# Arm_Power_Distro_Board.net
KiCad netlist of a schematic drawn in Altium Designer
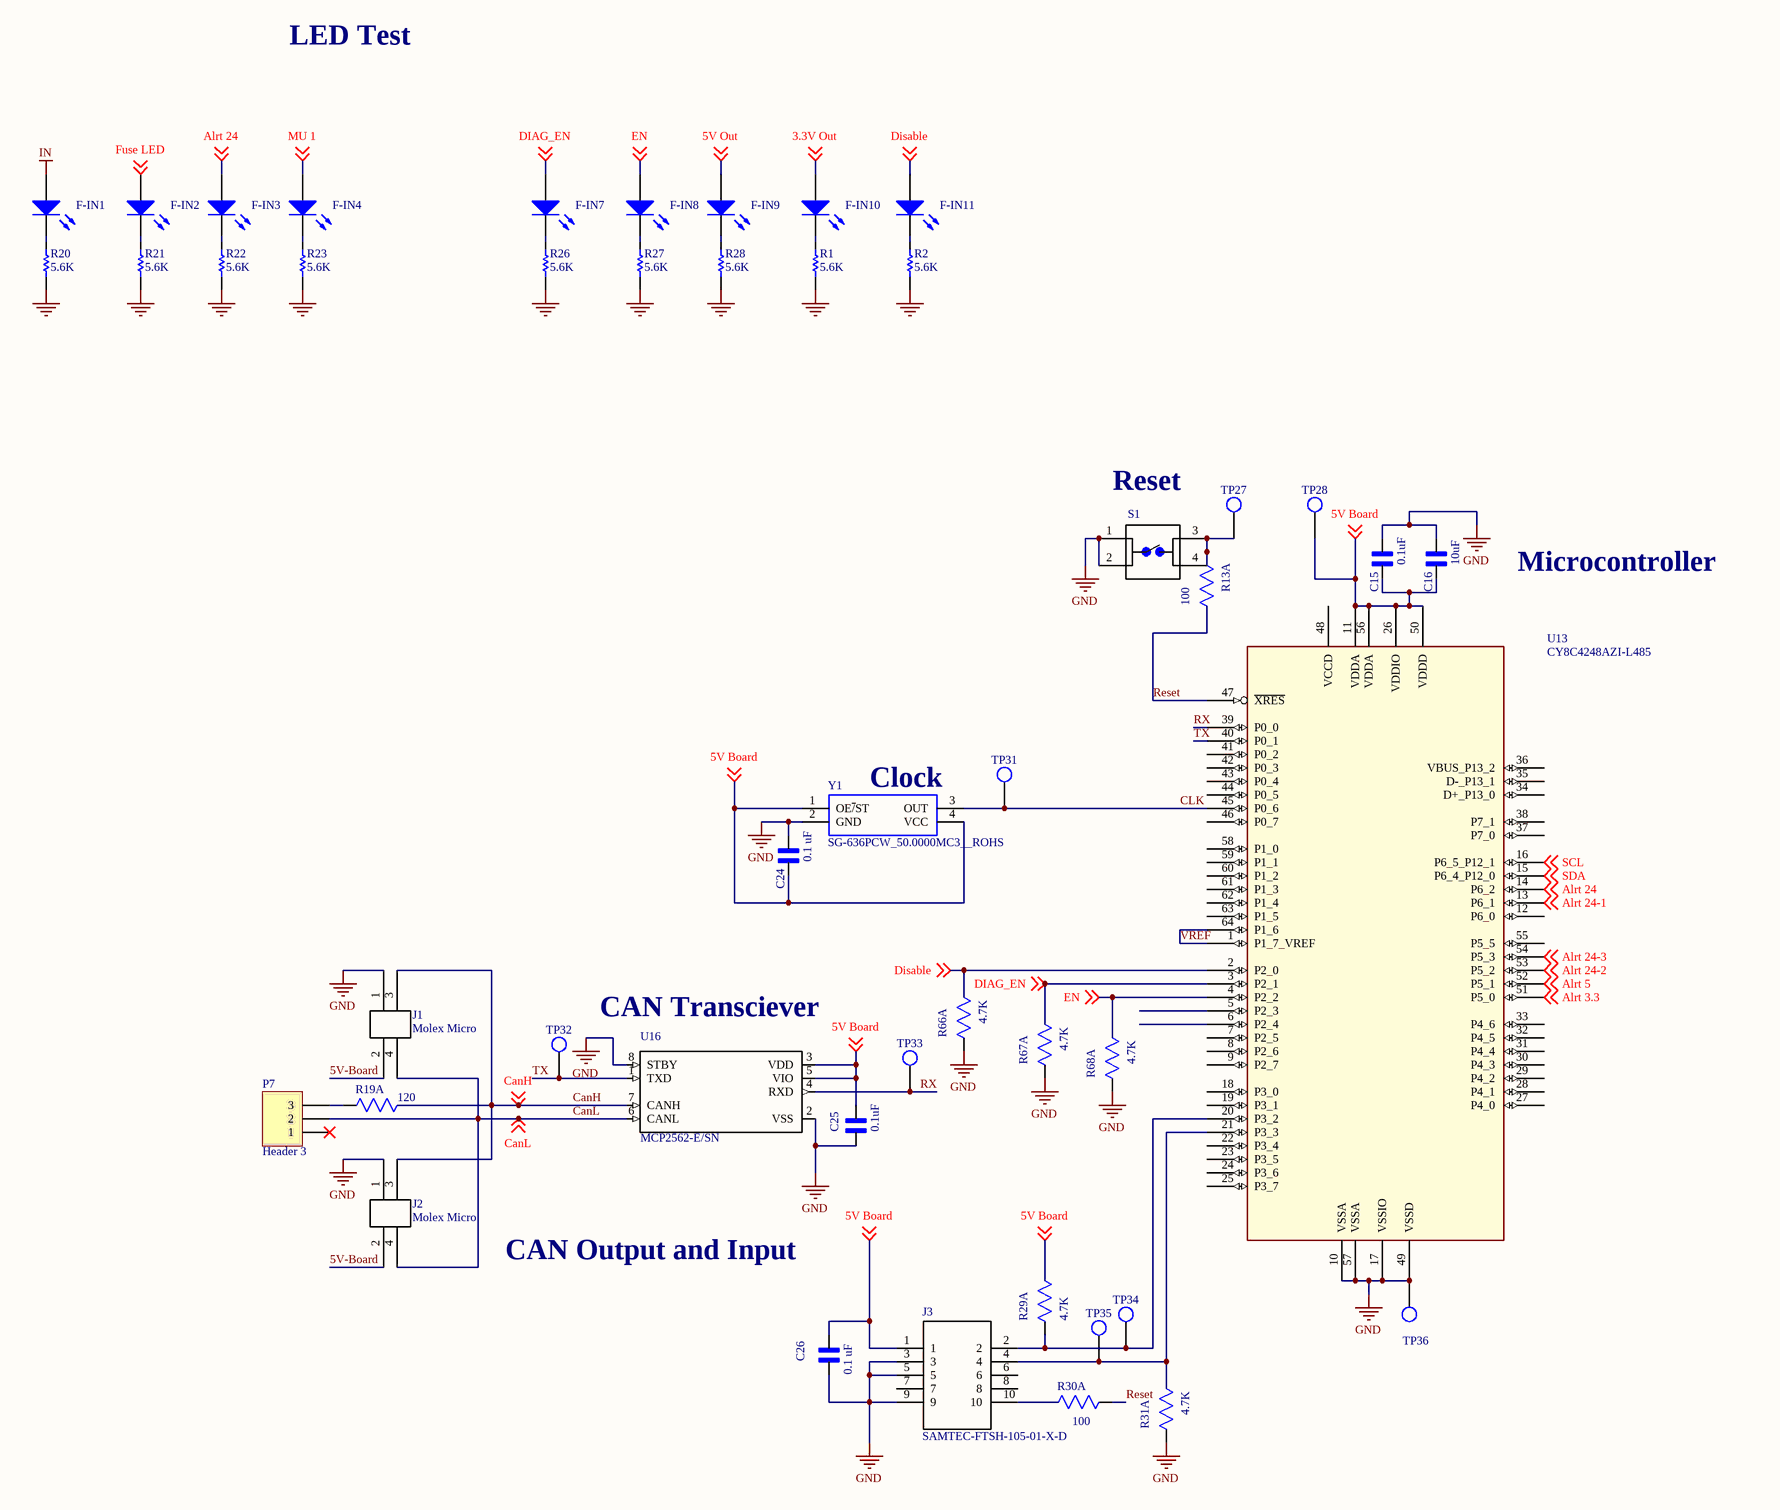
[diagram p0: Arm Power Distro Board (A).SchDoc]

(export (version "E")
  (design (tool "Eeschema 10.0.6"))
  (components
    (comp (ref "C15")
      (value "0.1uF")
      (footprint "*CAPC2012X135N")
      (description "Cap Ceramic 2.2uF 16V X5R 10% SMD 0805 125Â°C Embossed T/R")
      (fields (field (name "MP") "EMK212BJ225KG-T") (field (name "DIGI-KEY_PART_NUMBER") "587-1293-1-ND"))
      (libsource (lib "EMK212BJ225KG-T") (part "EMK212BJ225KG-T"))
    )
    (comp (ref "C16")
      (value "10uF")
      (footprint "*CAPC2012X135N")
      (description "Cap Ceramic 2.2uF 16V X5R 10% SMD 0805 125Â°C Embossed T/R")
      (fields (field (name "MP") "EMK212BJ225KG-T") (field (name "DIGI-KEY_PART_NUMBER") "587-1293-1-ND"))
      (libsource (lib "EMK212BJ225KG-T") (part "EMK212BJ225KG-T"))
    )
    (comp (ref "C24")
      (value "0.1 uF")
      (footprint "*CAPC2012X135N")
      (description "Cap Ceramic 2.2uF 16V X5R 10% SMD 0805 125Â°C Embossed T/R")
      (fields (field (name "MP") "EMK212BJ225KG-T") (field (name "DIGI-KEY_PART_NUMBER") "587-1293-1-ND"))
      (libsource (lib "EMK212BJ225KG-T") (part "EMK212BJ225KG-T"))
    )
    (comp (ref "C25")
      (value "0.1uF")
      (footprint "*CAPC2012X135N")
      (description "Cap Ceramic 2.2uF 16V X5R 10% SMD 0805 125Â°C Embossed T/R")
      (fields (field (name "MP") "EMK212BJ225KG-T") (field (name "DIGI-KEY_PART_NUMBER") "587-1293-1-ND"))
      (libsource (lib "EMK212BJ225KG-T") (part "EMK212BJ225KG-T"))
    )
    (comp (ref "C26")
      (value "0.1 uF")
      (footprint "*CAPC2012X135N")
      (description "Cap Ceramic 2.2uF 16V X5R 10% SMD 0805 125Â°C Embossed T/R")
      (fields (field (name "MP") "EMK212BJ225KG-T") (field (name "DIGI-KEY_PART_NUMBER") "587-1293-1-ND"))
      (libsource (lib "EMK212BJ225KG-T") (part "EMK212BJ225KG-T"))
    )
    (comp (ref "F-IN1")
      (value "150060VS75000")
      (footprint "0603_A")
      (description "SMD mono-color Chip LED, WL-SMCW, Bright Green")
      (fields (field (name "MANUFACTURER") "Wuerth Elektronik"))
      (libsource (lib "Altium Content Vault") (part "WE-LED_K1A2-2"))
    )
    (comp (ref "F-IN2")
      (value "150060VS75000")
      (footprint "0603_A")
      (description "SMD mono-color Chip LED, WL-SMCW, Bright Green")
      (fields (field (name "MANUFACTURER") "Wuerth Elektronik"))
      (libsource (lib "Altium Content Vault") (part "WE-LED_K1A2-2"))
    )
    (comp (ref "F-IN3")
      (value "150060VS75000")
      (footprint "0603_A")
      (description "SMD mono-color Chip LED, WL-SMCW, Bright Green")
      (fields (field (name "MANUFACTURER") "Wuerth Elektronik"))
      (libsource (lib "Altium Content Vault") (part "WE-LED_K1A2-2"))
    )
    (comp (ref "F-IN4")
      (value "150060VS75000")
      (footprint "0603_A")
      (description "SMD mono-color Chip LED, WL-SMCW, Bright Green")
      (fields (field (name "MANUFACTURER") "Wuerth Elektronik"))
      (libsource (lib "Altium Content Vault") (part "WE-LED_K1A2-2"))
    )
    (comp (ref "F-IN7")
      (value "150060VS75000")
      (footprint "0603_A")
      (description "SMD mono-color Chip LED, WL-SMCW, Bright Green")
      (fields (field (name "MANUFACTURER") "Wuerth Elektronik"))
      (libsource (lib "Altium Content Vault") (part "WE-LED_K1A2-2"))
    )
    (comp (ref "F-IN8")
      (value "150060VS75000")
      (footprint "0603_A")
      (description "SMD mono-color Chip LED, WL-SMCW, Bright Green")
      (fields (field (name "MANUFACTURER") "Wuerth Elektronik"))
      (libsource (lib "Altium Content Vault") (part "WE-LED_K1A2-2"))
    )
    (comp (ref "F-IN9")
      (value "150060VS75000")
      (footprint "0603_A")
      (description "SMD mono-color Chip LED, WL-SMCW, Bright Green")
      (fields (field (name "MANUFACTURER") "Wuerth Elektronik"))
      (libsource (lib "Altium Content Vault") (part "WE-LED_K1A2-2"))
    )
    (comp (ref "F-IN10")
      (value "150060VS75000")
      (footprint "0603_A")
      (description "SMD mono-color Chip LED, WL-SMCW, Bright Green")
      (fields (field (name "MANUFACTURER") "Wuerth Elektronik"))
      (libsource (lib "Altium Content Vault") (part "WE-LED_K1A2-2"))
    )
    (comp (ref "F-IN11")
      (value "150060VS75000")
      (footprint "0603_A")
      (description "SMD mono-color Chip LED, WL-SMCW, Bright Green")
      (fields (field (name "MANUFACTURER") "Wuerth Elektronik"))
      (libsource (lib "Altium Content Vault") (part "WE-LED_K1A2-2"))
    )
    (comp (ref "J1")
      (value "Molex Micro")
      (footprint "0430450427")
      (description "Molex micro-fit 3.0, P/N 0430450427")
      (libsource (lib "Connector Schematic Symbols") (part "Molex micro-fit 4-pin (dual row schematic)"))
    )
    (comp (ref "J2")
      (value "Molex Micro")
      (footprint "0430450427")
      (description "Molex micro-fit 3.0, P/N 0430450427")
      (libsource (lib "Connector Schematic Symbols") (part "Molex micro-fit 4-pin (dual row schematic)"))
    )
    (comp (ref "J3")
      (value "SAMTEC-FTSH-105-01-X-D")
      (footprint "SAMTEC-FTSH-105-01-X-D")
      (libsource (lib "Connector Schematic Symbols") (part "SAMTEC-FTSH-105-01-X-D"))
    )
    (comp (ref "P7")
      (value "Header 3")
      (footprint "HDR1X3")
      (description "Header, 3-Pin")
      (fields (field (name "PUBLISHER") "Altium Limited"))
      (libsource (lib "Miscellaneous Connectors") (part "Header 3"))
    )
    (comp (ref "R1")
      (value "5.6K")
      (footprint "RESC2013X60X35ML10T20")
      (description "RES SMD 36K OHM 1% 1/8W 0805")
      (fields (field (name "MANUFACTURER") "Yageo") (field (name "PART NUMBER") "RC0805FR-0736KL"))
      (libsource (lib "Altium Content Vault") (part "RES"))
    )
    (comp (ref "R2")
      (value "5.6K")
      (footprint "RESC2013X60X35ML10T20")
      (description "RES SMD 36K OHM 1% 1/8W 0805")
      (fields (field (name "MANUFACTURER") "Yageo") (field (name "PART NUMBER") "RC0805FR-0736KL"))
      (libsource (lib "Altium Content Vault") (part "RES"))
    )
    (comp (ref "R13")
      (value "100")
      (footprint "RC0805N")
      (description "No Description Available")
      (fields
        (field (name "MANUFACTURER_PART_NUMBER") "CRCW0805681RFKEA_1")
        (field (name "COPYRIGHT") "Copyright (C) 2018 Accelerated Designs. All rights reserved")
      )
      (libsource (lib "2019-11-21_04-54-07") (part "CRCW0805681RFKEA"))
    )
    (comp (ref "R19")
      (value "120")
      (footprint "RC0805N")
      (description "No Description Available")
      (fields
        (field (name "MANUFACTURER_PART_NUMBER") "CRCW0805681RFKEA_1")
        (field (name "COPYRIGHT") "Copyright (C) 2018 Accelerated Designs. All rights reserved")
      )
      (libsource (lib "2019-11-21_04-54-07") (part "CRCW0805681RFKEA"))
    )
    (comp (ref "R20")
      (value "5.6K")
      (footprint "RESC2013X60X35ML10T20")
      (description "RES SMD 36K OHM 1% 1/8W 0805")
      (fields (field (name "MANUFACTURER") "Yageo") (field (name "PART NUMBER") "RC0805FR-0736KL"))
      (libsource (lib "Altium Content Vault") (part "RES"))
    )
    (comp (ref "R21")
      (value "5.6K")
      (footprint "RESC2013X60X35ML10T20")
      (description "RES SMD 36K OHM 1% 1/8W 0805")
      (fields (field (name "MANUFACTURER") "Yageo") (field (name "PART NUMBER") "RC0805FR-0736KL"))
      (libsource (lib "Altium Content Vault") (part "RES"))
    )
    (comp (ref "R22")
      (value "5.6K")
      (footprint "RESC2013X60X35ML10T20")
      (description "RES SMD 36K OHM 1% 1/8W 0805")
      (fields (field (name "MANUFACTURER") "Yageo") (field (name "PART NUMBER") "RC0805FR-0736KL"))
      (libsource (lib "Altium Content Vault") (part "RES"))
    )
    (comp (ref "R23")
      (value "5.6K")
      (footprint "RESC2013X60X35ML10T20")
      (description "RES SMD 36K OHM 1% 1/8W 0805")
      (fields (field (name "MANUFACTURER") "Yageo") (field (name "PART NUMBER") "RC0805FR-0736KL"))
      (libsource (lib "Altium Content Vault") (part "RES"))
    )
    (comp (ref "R26")
      (value "5.6K")
      (footprint "RESC2013X60X35ML10T20")
      (description "RES SMD 36K OHM 1% 1/8W 0805")
      (fields (field (name "MANUFACTURER") "Yageo") (field (name "PART NUMBER") "RC0805FR-0736KL"))
      (libsource (lib "Altium Content Vault") (part "RES"))
    )
    (comp (ref "R27")
      (value "5.6K")
      (footprint "RESC2013X60X35ML10T20")
      (description "RES SMD 36K OHM 1% 1/8W 0805")
      (fields (field (name "MANUFACTURER") "Yageo") (field (name "PART NUMBER") "RC0805FR-0736KL"))
      (libsource (lib "Altium Content Vault") (part "RES"))
    )
    (comp (ref "R28")
      (value "5.6K")
      (footprint "RESC2013X60X35ML10T20")
      (description "RES SMD 36K OHM 1% 1/8W 0805")
      (fields (field (name "MANUFACTURER") "Yageo") (field (name "PART NUMBER") "RC0805FR-0736KL"))
      (libsource (lib "Altium Content Vault") (part "RES"))
    )
    (comp (ref "R29")
      (value "4.7K")
      (footprint "RC0805N")
      (description "No Description Available")
      (fields
        (field (name "MANUFACTURER_PART_NUMBER") "CRCW0805681RFKEA_1")
        (field (name "COPYRIGHT") "Copyright (C) 2018 Accelerated Designs. All rights reserved")
      )
      (libsource (lib "2019-11-21_04-54-07") (part "CRCW0805681RFKEA"))
    )
    (comp (ref "R30")
      (value "100")
      (footprint "RC0805N")
      (description "No Description Available")
      (fields
        (field (name "MANUFACTURER_PART_NUMBER") "CRCW0805681RFKEA_1")
        (field (name "COPYRIGHT") "Copyright (C) 2018 Accelerated Designs. All rights reserved")
      )
      (libsource (lib "2019-11-21_04-54-07") (part "CRCW0805681RFKEA"))
    )
    (comp (ref "R31")
      (value "4.7K")
      (footprint "RC0805N")
      (description "No Description Available")
      (fields
        (field (name "MANUFACTURER_PART_NUMBER") "CRCW0805681RFKEA_1")
        (field (name "COPYRIGHT") "Copyright (C) 2018 Accelerated Designs. All rights reserved")
      )
      (libsource (lib "2019-11-21_04-54-07") (part "CRCW0805681RFKEA"))
    )
    (comp (ref "R66")
      (value "4.7K")
      (footprint "RC0805N")
      (description "No Description Available")
      (fields
        (field (name "MANUFACTURER_PART_NUMBER") "CRCW0805681RFKEA_1")
        (field (name "COPYRIGHT") "Copyright (C) 2018 Accelerated Designs. All rights reserved")
      )
      (libsource (lib "2019-11-21_04-54-07") (part "CRCW0805681RFKEA"))
    )
    (comp (ref "R67")
      (value "4.7K")
      (footprint "RC0805N")
      (description "No Description Available")
      (fields
        (field (name "MANUFACTURER_PART_NUMBER") "CRCW0805681RFKEA_1")
        (field (name "COPYRIGHT") "Copyright (C) 2018 Accelerated Designs. All rights reserved")
      )
      (libsource (lib "2019-11-21_04-54-07") (part "CRCW0805681RFKEA"))
    )
    (comp (ref "R68")
      (value "4.7K")
      (footprint "RC0805N")
      (description "No Description Available")
      (fields
        (field (name "MANUFACTURER_PART_NUMBER") "CRCW0805681RFKEA_1")
        (field (name "COPYRIGHT") "Copyright (C) 2018 Accelerated Designs. All rights reserved")
      )
      (libsource (lib "2019-11-21_04-54-07") (part "CRCW0805681RFKEA"))
    )
    (comp (ref "S1")
      (value "1825910-7")
      (footprint "Switch 6mm 24V (NO)")
      (description "FSM4JAH=6MM TACT SWITCH, HIGH TEMP")
      (fields (field (name "MF") "TE Connectivity") (field (name "DIGI-KEY_PART_NUMBER") "450-1804-ND"))
      (libsource (lib "Switch 6mm 24V") (part "Switch 6mm 24V (NO)"))
    )
    (comp (ref "TP27")
      (value "Test Point")
      (footprint "Test Point Through-hole")
      (libsource (lib "Test Points") (part "Test Point"))
    )
    (comp (ref "TP28")
      (value "Test Point")
      (footprint "Test Point Through-hole")
      (libsource (lib "Test Points") (part "Test Point"))
    )
    (comp (ref "TP31")
      (value "Test Point")
      (footprint "Test Point Through-hole")
      (libsource (lib "Test Points") (part "Test Point"))
    )
    (comp (ref "TP32")
      (value "Test Point")
      (footprint "Test Point Through-hole")
      (libsource (lib "Test Points") (part "Test Point"))
    )
    (comp (ref "TP33")
      (value "Test Point")
      (footprint "Test Point Through-hole")
      (libsource (lib "Test Points") (part "Test Point"))
    )
    (comp (ref "TP34")
      (value "Test Point")
      (footprint "Test Point Through-hole")
      (libsource (lib "Test Points") (part "Test Point"))
    )
    (comp (ref "TP35")
      (value "Test Point")
      (footprint "Test Point Through-hole")
      (libsource (lib "Test Points") (part "Test Point"))
    )
    (comp (ref "TP36")
      (value "Test Point")
      (footprint "Test Point Through-hole")
      (libsource (lib "Test Points") (part "Test Point"))
    )
    (comp (ref "U13")
      (value "CY8C4248AZI-L485")
      (footprint "TQFP50P1200X1200X160-64N")
      (libsource (lib "PSOC") (part "CY8C4248AZI-L485"))
    )
    (comp (ref "U16")
      (value "MCP2562-E/SN")
      (footprint "SOIC127P600X175-8N")
      (description "Microchip MCP2562-E/SN, CAN Transceiver 1MBps 1-channel IEC 61000-4-2, 8-Pin SOIC")
      (fields (field (name "MF") "Microchip"))
      (libsource (lib "CAN Tranceiver") (part "MCP2562-E/SN"))
    )
    (comp (ref "Y1")
      (value "SG-636PCW_50.0000MC3__ROHS")
      (footprint "SG-636")
      (description "Standard Clock Oscillators 50MHz 3.3Volt 100ppm -20C +70C")
      (fields (field (name "MANUFACTURER_PART_NUMBER") "SG-636PCW 50.0000MC3: ROHS"))
      (libsource (lib "Oscillator") (part "SG-636"))
    )
  )
  (nets
    (net (code "1") (name "/5V-Board") (class "Default")
      (node (ref "J1") (pin "2") (pintype "passive"))
      (node (ref "J2") (pin "2") (pintype "passive"))
    )
    (net (code "2") (name "/CLK") (class "Default")
      (node (ref "TP31") (pin "1") (pinfunction "1_1") (pintype "passive"))
      (node (ref "U13") (pin "45") (pinfunction "P0_6_45") (pintype "bidirectional"))
      (node (ref "Y1") (pin "3") (pinfunction "OUT_3") (pintype "passive"))
    )
    (net (code "3") (name "/RX") (class "Default")
      (node (ref "TP33") (pin "1") (pinfunction "1_1") (pintype "passive"))
      (node (ref "U13") (pin "39") (pinfunction "P0_0_39") (pintype "bidirectional"))
      (node (ref "U16") (pin "4") (pinfunction "RXD_4") (pintype "output"))
    )
    (net (code "4") (name "/Reset") (class "Default")
      (node (ref "R13") (pin "2") (pinfunction "2_2") (pintype "passive"))
      (node (ref "R30") (pin "1") (pinfunction "1_1") (pintype "passive"))
      (node (ref "U13") (pin "47") (pinfunction "~{XRES}_47") (pintype "input"))
    )
    (net (code "5") (name "/TX") (class "Default")
      (node (ref "TP32") (pin "1") (pinfunction "1_1") (pintype "passive"))
      (node (ref "U13") (pin "40") (pinfunction "P0_1_40") (pintype "bidirectional"))
      (node (ref "U16") (pin "1") (pinfunction "TXD_1") (pintype "input"))
    )
    (net (code "6") (name "/VREF") (class "Default")
      (node (ref "U13") (pin "1") (pinfunction "P1_7_VREF_1") (pintype "bidirectional"))
      (node (ref "U13") (pin "64") (pinfunction "P1_6_64") (pintype "bidirectional"))
    )
    (net (code "7") (name "3.3V Out") (class "Default")
      (node (ref "F-IN10") (pin "2") (pinfunction "A_2") (pintype "passive"))
    )
    (net (code "8") (name "5V Board") (class "Default")
      (node (ref "C15") (pin "1") (pinfunction "1_1") (pintype "passive"))
      (node (ref "C16") (pin "1") (pinfunction "1_1") (pintype "passive"))
      (node (ref "C24") (pin "1") (pinfunction "1_1") (pintype "passive"))
      (node (ref "C25") (pin "2") (pinfunction "2_2") (pintype "passive"))
      (node (ref "C26") (pin "2") (pinfunction "2_2") (pintype "passive"))
      (node (ref "J3") (pin "1") (pinfunction "1_1") (pintype "passive"))
      (node (ref "R29") (pin "2") (pinfunction "2_2") (pintype "passive"))
      (node (ref "TP28") (pin "1") (pinfunction "1_1") (pintype "passive"))
      (node (ref "U13") (pin "11") (pinfunction "VDDA_11") (pintype "power_in"))
      (node (ref "U13") (pin "26") (pinfunction "VDDIO_26") (pintype "power_in"))
      (node (ref "U13") (pin "50") (pinfunction "VDDD_50") (pintype "power_in"))
      (node (ref "U13") (pin "56") (pinfunction "VDDA_56") (pintype "power_in"))
      (node (ref "U16") (pin "3") (pinfunction "VDD_3") (pintype "power_in"))
      (node (ref "U16") (pin "5") (pinfunction "VIO_5") (pintype "power_in"))
      (node (ref "Y1") (pin "1") (pinfunction "OE~{/}ST_1") (pintype "passive"))
      (node (ref "Y1") (pin "4") (pinfunction "VCC_4") (pintype "power_in"))
    )
    (net (code "9") (name "5V Out") (class "Default")
      (node (ref "F-IN9") (pin "2") (pinfunction "A_2") (pintype "passive"))
    )
    (net (code "10") (name "Alrt 3.3") (class "Default")
      (node (ref "U13") (pin "51") (pinfunction "P5_0_51") (pintype "bidirectional"))
    )
    (net (code "11") (name "Alrt 5") (class "Default")
      (node (ref "U13") (pin "52") (pinfunction "P5_1_52") (pintype "bidirectional"))
    )
    (net (code "12") (name "Alrt 24") (class "Default")
      (node (ref "F-IN3") (pin "2") (pinfunction "A_2") (pintype "passive"))
      (node (ref "U13") (pin "14") (pinfunction "P6_2_14") (pintype "bidirectional"))
    )
    (net (code "13") (name "Alrt 24-1") (class "Default")
      (node (ref "U13") (pin "13") (pinfunction "P6_1_13") (pintype "bidirectional"))
    )
    (net (code "14") (name "Alrt 24-2") (class "Default")
      (node (ref "U13") (pin "53") (pinfunction "P5_2_53") (pintype "bidirectional"))
    )
    (net (code "15") (name "Alrt 24-3") (class "Default")
      (node (ref "U13") (pin "54") (pinfunction "P5_3_54") (pintype "bidirectional"))
    )
    (net (code "16") (name "CanH") (class "Default")
      (node (ref "J1") (pin "3") (pintype "passive"))
      (node (ref "J2") (pin "3") (pintype "passive"))
      (node (ref "R19") (pin "2") (pinfunction "2_2") (pintype "passive"))
      (node (ref "U16") (pin "7") (pinfunction "CANH_7") (pintype "input"))
    )
    (net (code "17") (name "CanL") (class "Default")
      (node (ref "J1") (pin "4") (pintype "passive"))
      (node (ref "J2") (pin "4") (pintype "passive"))
      (node (ref "P7") (pin "2") (pinfunction "2_2") (pintype "passive"))
      (node (ref "U16") (pin "6") (pinfunction "CANL_6") (pintype "input"))
    )
    (net (code "18") (name "DIAG_EN") (class "Default")
      (node (ref "F-IN7") (pin "2") (pinfunction "A_2") (pintype "passive"))
      (node (ref "R67") (pin "2") (pinfunction "2_2") (pintype "passive"))
      (node (ref "U13") (pin "3") (pinfunction "P2_1_3") (pintype "bidirectional"))
    )
    (net (code "19") (name "Disable") (class "Default")
      (node (ref "F-IN11") (pin "2") (pinfunction "A_2") (pintype "passive"))
      (node (ref "R66") (pin "2") (pinfunction "2_2") (pintype "passive"))
      (node (ref "U13") (pin "2") (pinfunction "P2_0_2") (pintype "bidirectional"))
    )
    (net (code "20") (name "EN") (class "Default")
      (node (ref "F-IN8") (pin "2") (pinfunction "A_2") (pintype "passive"))
      (node (ref "R68") (pin "2") (pinfunction "2_2") (pintype "passive"))
      (node (ref "U13") (pin "4") (pinfunction "P2_2_4") (pintype "bidirectional"))
    )
    (net (code "21") (name "Fuse LED") (class "Default")
      (node (ref "F-IN2") (pin "2") (pinfunction "A_2") (pintype "passive"))
    )
    (net (code "22") (name "GND") (class "Default")
      (node (ref "C15") (pin "2") (pinfunction "2_2") (pintype "passive"))
      (node (ref "C16") (pin "2") (pinfunction "2_2") (pintype "passive"))
      (node (ref "C24") (pin "2") (pinfunction "2_2") (pintype "passive"))
      (node (ref "C25") (pin "1") (pinfunction "1_1") (pintype "passive"))
      (node (ref "C26") (pin "1") (pinfunction "1_1") (pintype "passive"))
      (node (ref "J1") (pin "1") (pintype "passive"))
      (node (ref "J2") (pin "1") (pintype "passive"))
      (node (ref "J3") (pin "3") (pinfunction "3_3") (pintype "passive"))
      (node (ref "J3") (pin "5") (pinfunction "5_5") (pintype "passive"))
      (node (ref "J3") (pin "9") (pinfunction "9_9") (pintype "passive"))
      (node (ref "R1") (pin "1") (pinfunction "1_1") (pintype "passive"))
      (node (ref "R2") (pin "1") (pinfunction "1_1") (pintype "passive"))
      (node (ref "R20") (pin "1") (pinfunction "1_1") (pintype "passive"))
      (node (ref "R21") (pin "1") (pinfunction "1_1") (pintype "passive"))
      (node (ref "R22") (pin "1") (pinfunction "1_1") (pintype "passive"))
      (node (ref "R23") (pin "1") (pinfunction "1_1") (pintype "passive"))
      (node (ref "R26") (pin "1") (pinfunction "1_1") (pintype "passive"))
      (node (ref "R27") (pin "1") (pinfunction "1_1") (pintype "passive"))
      (node (ref "R28") (pin "1") (pinfunction "1_1") (pintype "passive"))
      (node (ref "R31") (pin "1") (pinfunction "1_1") (pintype "passive"))
      (node (ref "R66") (pin "1") (pinfunction "1_1") (pintype "passive"))
      (node (ref "R67") (pin "1") (pinfunction "1_1") (pintype "passive"))
      (node (ref "R68") (pin "1") (pinfunction "1_1") (pintype "passive"))
      (node (ref "S1") (pin "1") (pinfunction "1_1") (pintype "passive"))
      (node (ref "S1") (pin "2") (pinfunction "2_2") (pintype "passive"))
      (node (ref "TP36") (pin "1") (pinfunction "1_1") (pintype "passive"))
      (node (ref "U13") (pin "10") (pinfunction "VSSA_10") (pintype "power_in"))
      (node (ref "U13") (pin "17") (pinfunction "VSSIO_17") (pintype "power_in"))
      (node (ref "U13") (pin "49") (pinfunction "VSSD_49") (pintype "power_in"))
      (node (ref "U13") (pin "57") (pinfunction "VSSA_57") (pintype "power_in"))
      (node (ref "U16") (pin "2") (pinfunction "VSS_2") (pintype "power_in"))
      (node (ref "U16") (pin "8") (pinfunction "STBY_8") (pintype "input"))
      (node (ref "Y1") (pin "2") (pinfunction "GND_2") (pintype "passive"))
    )
    (net (code "23") (name "IN") (class "Default")
      (node (ref "F-IN1") (pin "2") (pinfunction "A_2") (pintype "passive"))
    )
    (net (code "24") (name "MU 1") (class "Default")
      (node (ref "F-IN4") (pin "2") (pinfunction "A_2") (pintype "passive"))
    )
    (net (code "25") (name "Net-(F-IN1-K)") (class "Default")
      (node (ref "F-IN1") (pin "1") (pinfunction "K_1") (pintype "passive"))
      (node (ref "R20") (pin "2") (pinfunction "2_2") (pintype "passive"))
    )
    (net (code "26") (name "Net-(F-IN2-K)") (class "Default")
      (node (ref "F-IN2") (pin "1") (pinfunction "K_1") (pintype "passive"))
      (node (ref "R21") (pin "2") (pinfunction "2_2") (pintype "passive"))
    )
    (net (code "27") (name "Net-(F-IN3-K)") (class "Default")
      (node (ref "F-IN3") (pin "1") (pinfunction "K_1") (pintype "passive"))
      (node (ref "R22") (pin "2") (pinfunction "2_2") (pintype "passive"))
    )
    (net (code "28") (name "Net-(F-IN4-K)") (class "Default")
      (node (ref "F-IN4") (pin "1") (pinfunction "K_1") (pintype "passive"))
      (node (ref "R23") (pin "2") (pinfunction "2_2") (pintype "passive"))
    )
    (net (code "29") (name "Net-(F-IN7-K)") (class "Default")
      (node (ref "F-IN7") (pin "1") (pinfunction "K_1") (pintype "passive"))
      (node (ref "R26") (pin "2") (pinfunction "2_2") (pintype "passive"))
    )
    (net (code "30") (name "Net-(F-IN8-K)") (class "Default")
      (node (ref "F-IN8") (pin "1") (pinfunction "K_1") (pintype "passive"))
      (node (ref "R27") (pin "2") (pinfunction "2_2") (pintype "passive"))
    )
    (net (code "31") (name "Net-(F-IN9-K)") (class "Default")
      (node (ref "F-IN9") (pin "1") (pinfunction "K_1") (pintype "passive"))
      (node (ref "R28") (pin "2") (pinfunction "2_2") (pintype "passive"))
    )
    (net (code "32") (name "Net-(F-IN10-K)") (class "Default")
      (node (ref "F-IN10") (pin "1") (pinfunction "K_1") (pintype "passive"))
      (node (ref "R1") (pin "2") (pinfunction "2_2") (pintype "passive"))
    )
    (net (code "33") (name "Net-(F-IN11-K)") (class "Default")
      (node (ref "F-IN11") (pin "1") (pinfunction "K_1") (pintype "passive"))
      (node (ref "R2") (pin "2") (pinfunction "2_2") (pintype "passive"))
    )
    (net (code "34") (name "Net-(J3-Pad10)") (class "Default")
      (node (ref "J3") (pin "10") (pinfunction "10_10") (pintype "passive"))
      (node (ref "R30") (pin "2") (pinfunction "2_2") (pintype "passive"))
    )
    (net (code "35") (name "Net-(P7-Pad3)") (class "Default")
      (node (ref "P7") (pin "3") (pinfunction "3_3") (pintype "passive"))
      (node (ref "R19") (pin "1") (pinfunction "1_1") (pintype "passive"))
    )
    (net (code "36") (name "Net-(R13-Pad1)") (class "Default")
      (node (ref "R13") (pin "1") (pinfunction "1_1") (pintype "passive"))
      (node (ref "S1") (pin "3") (pinfunction "3_3") (pintype "passive"))
      (node (ref "S1") (pin "4") (pinfunction "4_4") (pintype "passive"))
      (node (ref "TP27") (pin "1") (pinfunction "1_1") (pintype "passive"))
    )
    (net (code "37") (name "Net-(U13-P3_2)") (class "Default")
      (node (ref "J3") (pin "2") (pinfunction "2_2") (pintype "passive"))
      (node (ref "R29") (pin "1") (pinfunction "1_1") (pintype "passive"))
      (node (ref "TP34") (pin "1") (pinfunction "1_1") (pintype "passive"))
      (node (ref "U13") (pin "20") (pinfunction "P3_2_20") (pintype "bidirectional"))
    )
    (net (code "38") (name "Net-(U13-P3_3)") (class "Default")
      (node (ref "J3") (pin "4") (pinfunction "4_4") (pintype "passive"))
      (node (ref "R31") (pin "2") (pinfunction "2_2") (pintype "passive"))
      (node (ref "TP35") (pin "1") (pinfunction "1_1") (pintype "passive"))
      (node (ref "U13") (pin "21") (pinfunction "P3_3_21") (pintype "bidirectional"))
    )
    (net (code "39") (name "SCL") (class "Default")
      (node (ref "U13") (pin "16") (pinfunction "P6_5_P12_1_16") (pintype "bidirectional"))
    )
    (net (code "40") (name "SDA") (class "Default")
      (node (ref "U13") (pin "15") (pinfunction "P6_4_P12_0_15") (pintype "bidirectional"))
    )
    (net (code "41") (name "unconnected-(J3-Pad6)") (class "Default")
      (node (ref "J3") (pin "6") (pinfunction "6_6") (pintype "passive"))
    )
    (net (code "42") (name "unconnected-(J3-Pad7)") (class "Default")
      (node (ref "J3") (pin "7") (pinfunction "7_7") (pintype "passive"))
    )
    (net (code "43") (name "unconnected-(J3-Pad8)") (class "Default")
      (node (ref "J3") (pin "8") (pinfunction "8_8") (pintype "passive"))
    )
    (net (code "44") (name "unconnected-(P7-Pad1)") (class "Default")
      (node (ref "P7") (pin "1") (pinfunction "1_1") (pintype "passive+no_connect"))
    )
    (net (code "45") (name "unconnected-(U13-D+_P13_0-Pad34)") (class "Default")
      (node (ref "U13") (pin "34") (pinfunction "D+_P13_0_34") (pintype "bidirectional"))
    )
    (net (code "46") (name "unconnected-(U13-D-_P13_1-Pad35)") (class "Default")
      (node (ref "U13") (pin "35") (pinfunction "D-_P13_1_35") (pintype "bidirectional"))
    )
    (net (code "47") (name "unconnected-(U13-P0_2-Pad41)") (class "Default")
      (node (ref "U13") (pin "41") (pinfunction "P0_2_41") (pintype "bidirectional"))
    )
    (net (code "48") (name "unconnected-(U13-P0_3-Pad42)") (class "Default")
      (node (ref "U13") (pin "42") (pinfunction "P0_3_42") (pintype "bidirectional"))
    )
    (net (code "49") (name "unconnected-(U13-P0_4-Pad43)") (class "Default")
      (node (ref "U13") (pin "43") (pinfunction "P0_4_43") (pintype "bidirectional"))
    )
    (net (code "50") (name "unconnected-(U13-P0_5-Pad44)") (class "Default")
      (node (ref "U13") (pin "44") (pinfunction "P0_5_44") (pintype "bidirectional"))
    )
    (net (code "51") (name "unconnected-(U13-P0_7-Pad46)") (class "Default")
      (node (ref "U13") (pin "46") (pinfunction "P0_7_46") (pintype "bidirectional"))
    )
    (net (code "52") (name "unconnected-(U13-P1_0-Pad58)") (class "Default")
      (node (ref "U13") (pin "58") (pinfunction "P1_0_58") (pintype "bidirectional"))
    )
    (net (code "53") (name "unconnected-(U13-P1_1-Pad59)") (class "Default")
      (node (ref "U13") (pin "59") (pinfunction "P1_1_59") (pintype "bidirectional"))
    )
    (net (code "54") (name "unconnected-(U13-P1_2-Pad60)") (class "Default")
      (node (ref "U13") (pin "60") (pinfunction "P1_2_60") (pintype "bidirectional"))
    )
    (net (code "55") (name "unconnected-(U13-P1_3-Pad61)") (class "Default")
      (node (ref "U13") (pin "61") (pinfunction "P1_3_61") (pintype "bidirectional"))
    )
    (net (code "56") (name "unconnected-(U13-P1_4-Pad62)") (class "Default")
      (node (ref "U13") (pin "62") (pinfunction "P1_4_62") (pintype "bidirectional"))
    )
    (net (code "57") (name "unconnected-(U13-P1_5-Pad63)") (class "Default")
      (node (ref "U13") (pin "63") (pinfunction "P1_5_63") (pintype "bidirectional"))
    )
    (net (code "58") (name "unconnected-(U13-P2_3-Pad5)") (class "Default")
      (node (ref "U13") (pin "5") (pinfunction "P2_3_5") (pintype "bidirectional"))
    )
    (net (code "59") (name "unconnected-(U13-P2_4-Pad6)") (class "Default")
      (node (ref "U13") (pin "6") (pinfunction "P2_4_6") (pintype "bidirectional"))
    )
    (net (code "60") (name "unconnected-(U13-P2_5-Pad7)") (class "Default")
      (node (ref "U13") (pin "7") (pinfunction "P2_5_7") (pintype "bidirectional"))
    )
    (net (code "61") (name "unconnected-(U13-P2_6-Pad8)") (class "Default")
      (node (ref "U13") (pin "8") (pinfunction "P2_6_8") (pintype "bidirectional"))
    )
    (net (code "62") (name "unconnected-(U13-P2_7-Pad9)") (class "Default")
      (node (ref "U13") (pin "9") (pinfunction "P2_7_9") (pintype "bidirectional"))
    )
    (net (code "63") (name "unconnected-(U13-P3_0-Pad18)") (class "Default")
      (node (ref "U13") (pin "18") (pinfunction "P3_0_18") (pintype "bidirectional"))
    )
    (net (code "64") (name "unconnected-(U13-P3_1-Pad19)") (class "Default")
      (node (ref "U13") (pin "19") (pinfunction "P3_1_19") (pintype "bidirectional"))
    )
    (net (code "65") (name "unconnected-(U13-P3_4-Pad22)") (class "Default")
      (node (ref "U13") (pin "22") (pinfunction "P3_4_22") (pintype "bidirectional"))
    )
    (net (code "66") (name "unconnected-(U13-P3_5-Pad23)") (class "Default")
      (node (ref "U13") (pin "23") (pinfunction "P3_5_23") (pintype "bidirectional"))
    )
    (net (code "67") (name "unconnected-(U13-P3_6-Pad24)") (class "Default")
      (node (ref "U13") (pin "24") (pinfunction "P3_6_24") (pintype "bidirectional"))
    )
    (net (code "68") (name "unconnected-(U13-P3_7-Pad25)") (class "Default")
      (node (ref "U13") (pin "25") (pinfunction "P3_7_25") (pintype "bidirectional"))
    )
    (net (code "69") (name "unconnected-(U13-P4_0-Pad27)") (class "Default")
      (node (ref "U13") (pin "27") (pinfunction "P4_0_27") (pintype "bidirectional"))
    )
    (net (code "70") (name "unconnected-(U13-P4_1-Pad28)") (class "Default")
      (node (ref "U13") (pin "28") (pinfunction "P4_1_28") (pintype "bidirectional"))
    )
    (net (code "71") (name "unconnected-(U13-P4_2-Pad29)") (class "Default")
      (node (ref "U13") (pin "29") (pinfunction "P4_2_29") (pintype "bidirectional"))
    )
    (net (code "72") (name "unconnected-(U13-P4_3-Pad30)") (class "Default")
      (node (ref "U13") (pin "30") (pinfunction "P4_3_30") (pintype "bidirectional"))
    )
    (net (code "73") (name "unconnected-(U13-P4_4-Pad31)") (class "Default")
      (node (ref "U13") (pin "31") (pinfunction "P4_4_31") (pintype "bidirectional"))
    )
    (net (code "74") (name "unconnected-(U13-P4_5-Pad32)") (class "Default")
      (node (ref "U13") (pin "32") (pinfunction "P4_5_32") (pintype "bidirectional"))
    )
    (net (code "75") (name "unconnected-(U13-P4_6-Pad33)") (class "Default")
      (node (ref "U13") (pin "33") (pinfunction "P4_6_33") (pintype "bidirectional"))
    )
    (net (code "76") (name "unconnected-(U13-P5_5-Pad55)") (class "Default")
      (node (ref "U13") (pin "55") (pinfunction "P5_5_55") (pintype "bidirectional"))
    )
    (net (code "77") (name "unconnected-(U13-P6_0-Pad12)") (class "Default")
      (node (ref "U13") (pin "12") (pinfunction "P6_0_12") (pintype "bidirectional"))
    )
    (net (code "78") (name "unconnected-(U13-P7_0-Pad37)") (class "Default")
      (node (ref "U13") (pin "37") (pinfunction "P7_0_37") (pintype "bidirectional"))
    )
    (net (code "79") (name "unconnected-(U13-P7_1-Pad38)") (class "Default")
      (node (ref "U13") (pin "38") (pinfunction "P7_1_38") (pintype "bidirectional"))
    )
    (net (code "80") (name "unconnected-(U13-VBUS_P13_2-Pad36)") (class "Default")
      (node (ref "U13") (pin "36") (pinfunction "VBUS_P13_2_36") (pintype "bidirectional"))
    )
    (net (code "81") (name "unconnected-(U13-VCCD-Pad48)") (class "Default")
      (node (ref "U13") (pin "48") (pinfunction "VCCD_48") (pintype "power_in"))
    )
  )
)
